# Power_board_rev_2.net
KiCad netlist of a schematic drawn in EAGLE
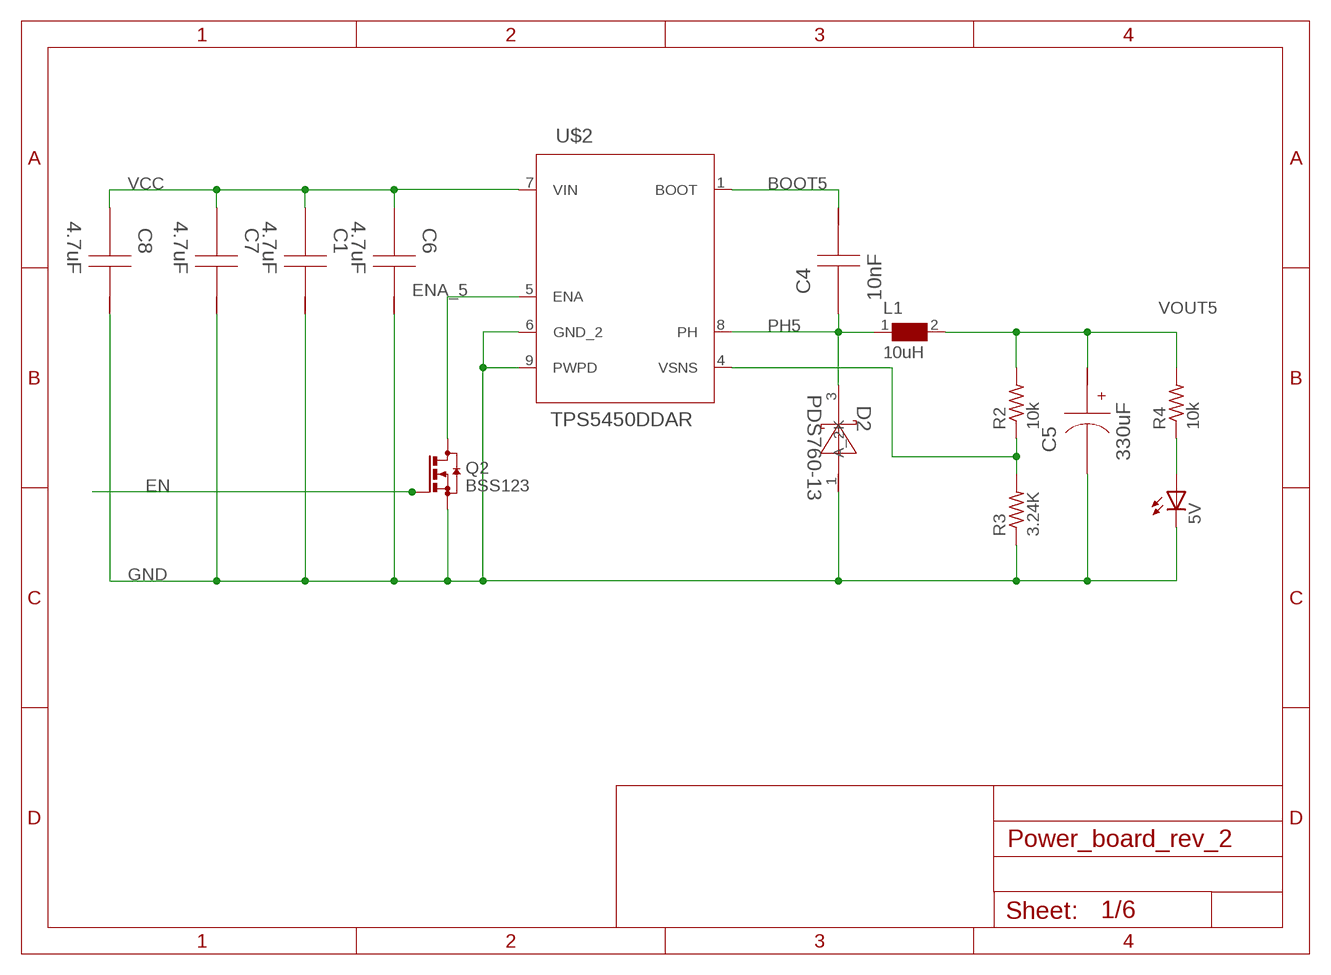
[diagram p0: schematic, sheet 1]
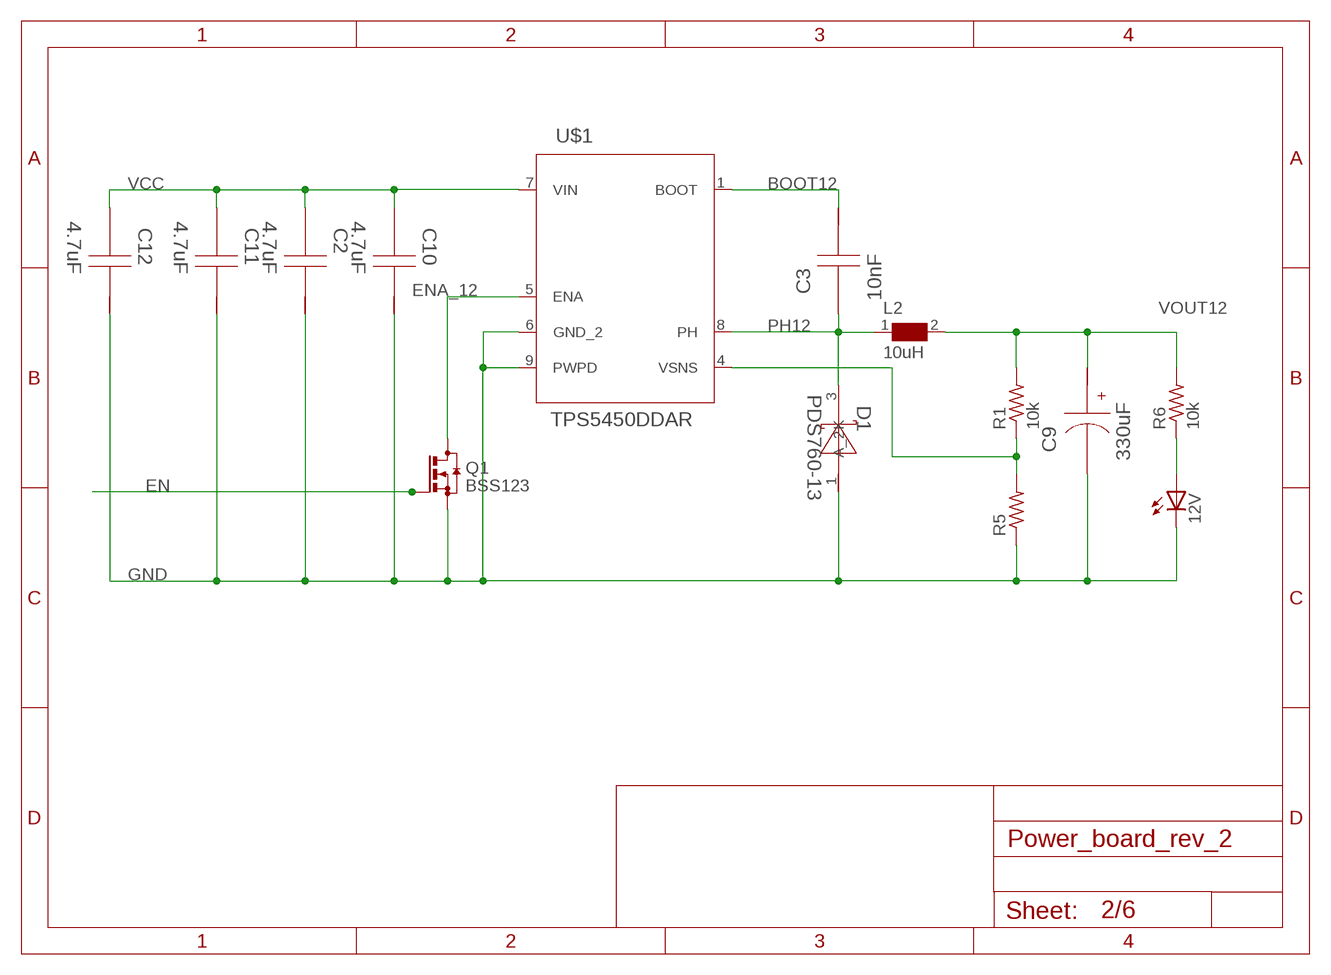
[diagram p1: schematic, sheet 2]
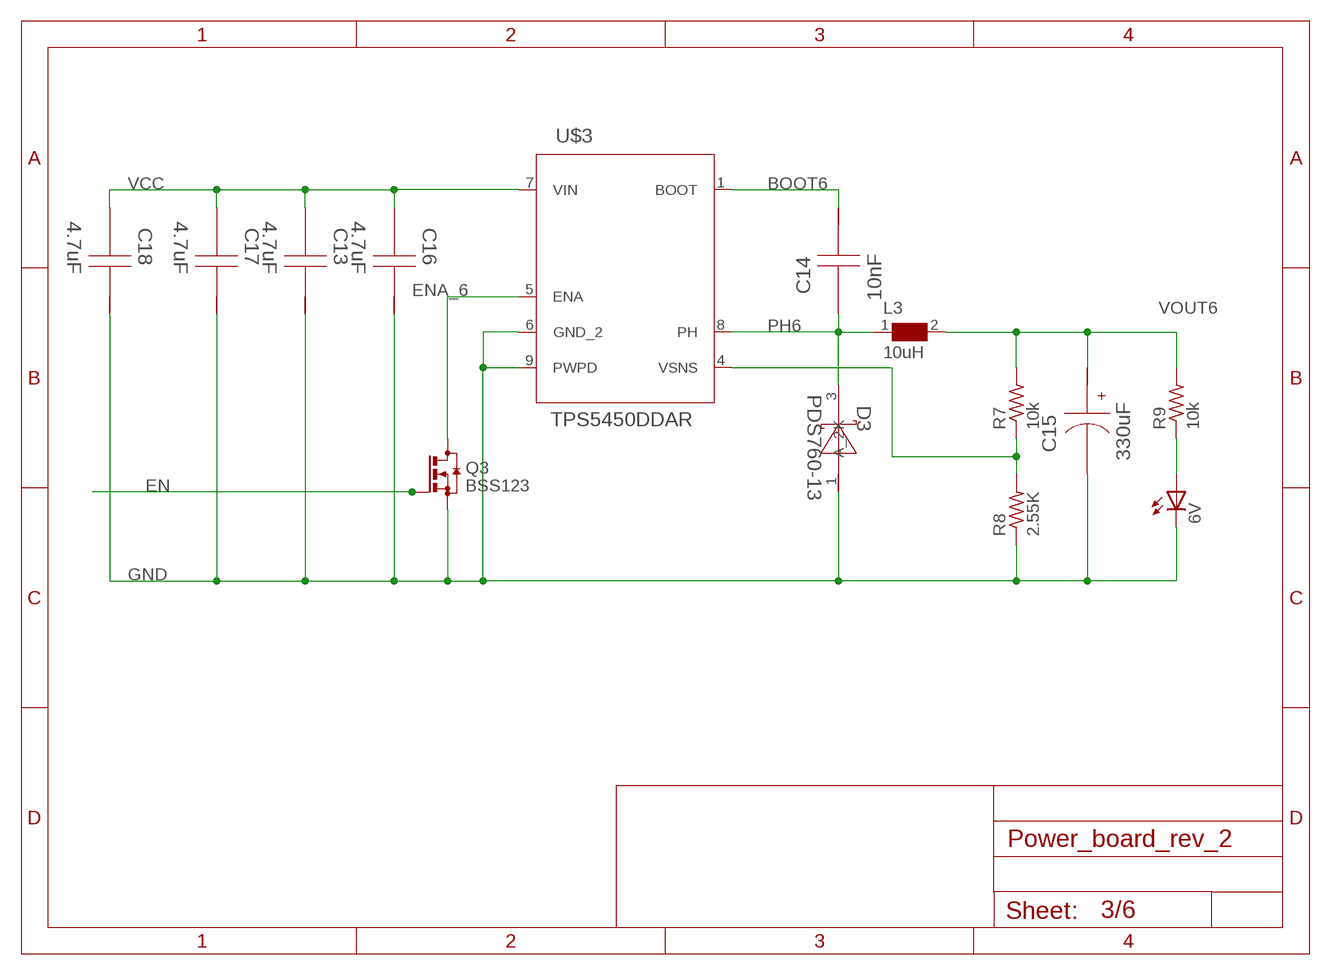
[diagram p2: schematic, sheet 3]
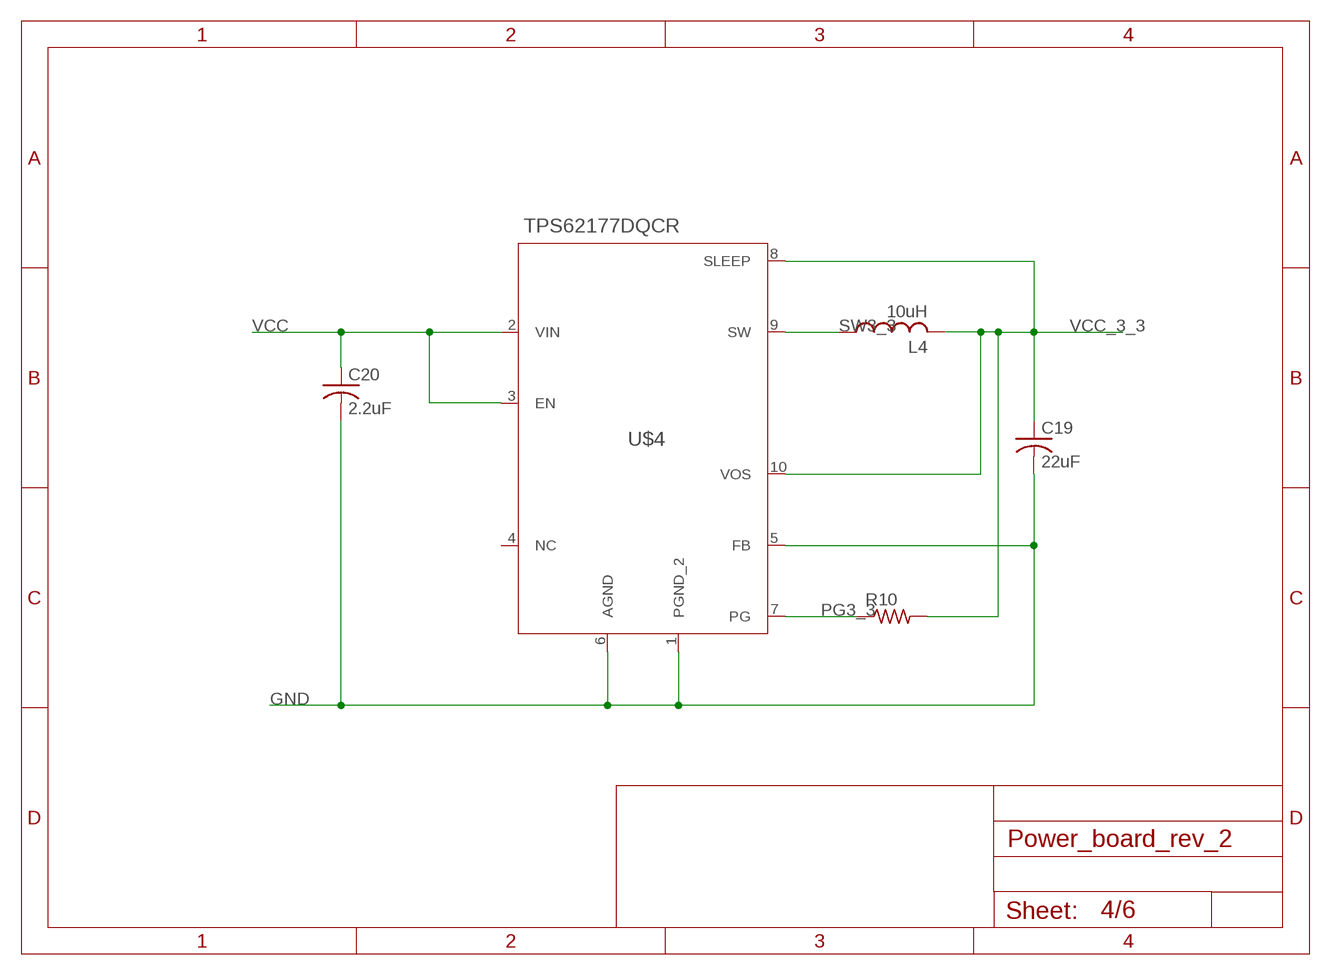
[diagram p3: schematic, sheet 4]
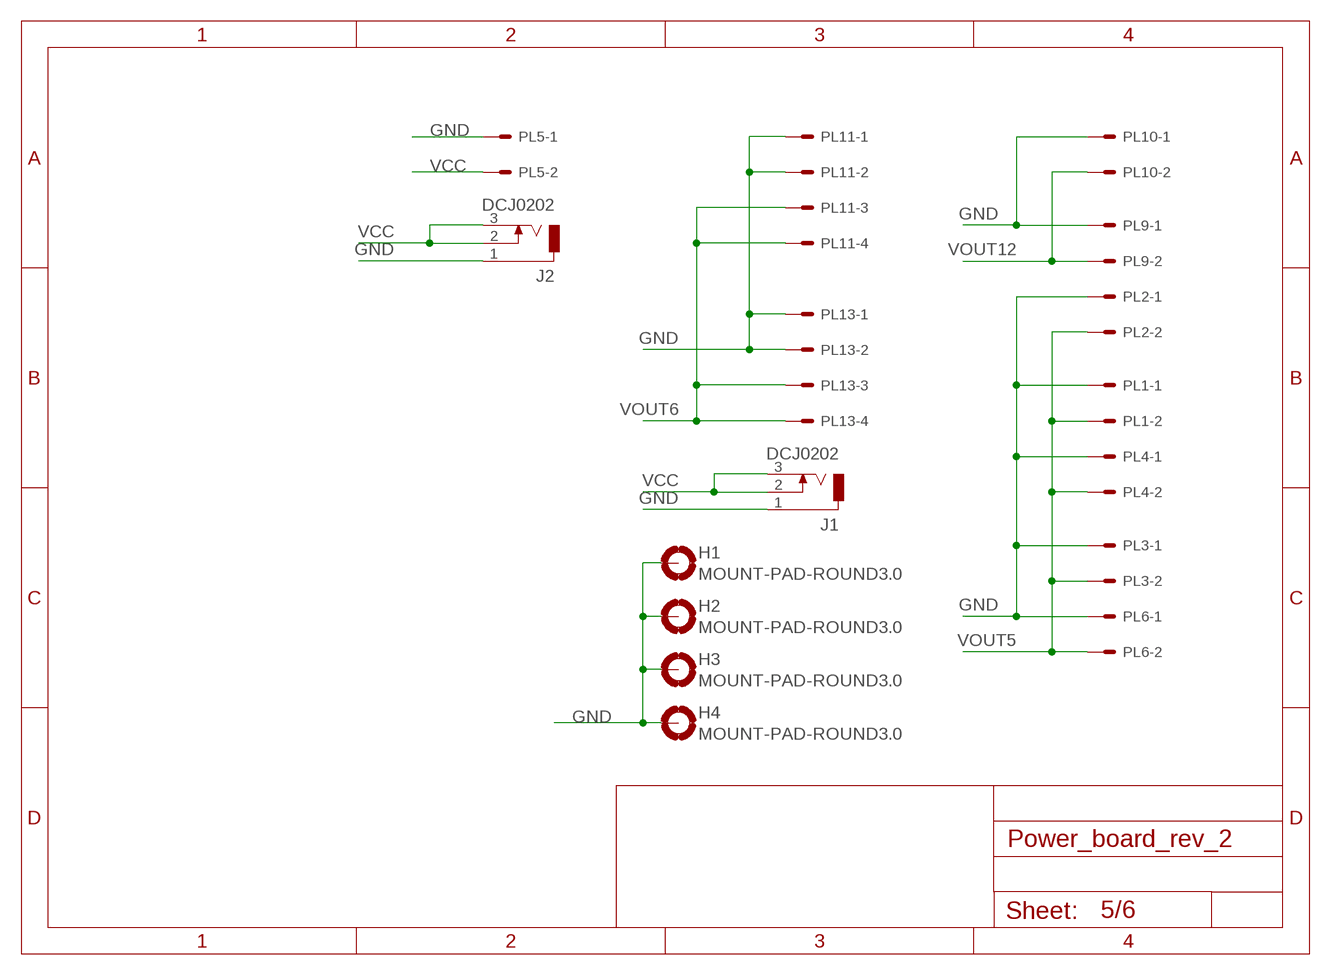
[diagram p4: schematic, sheet 5]
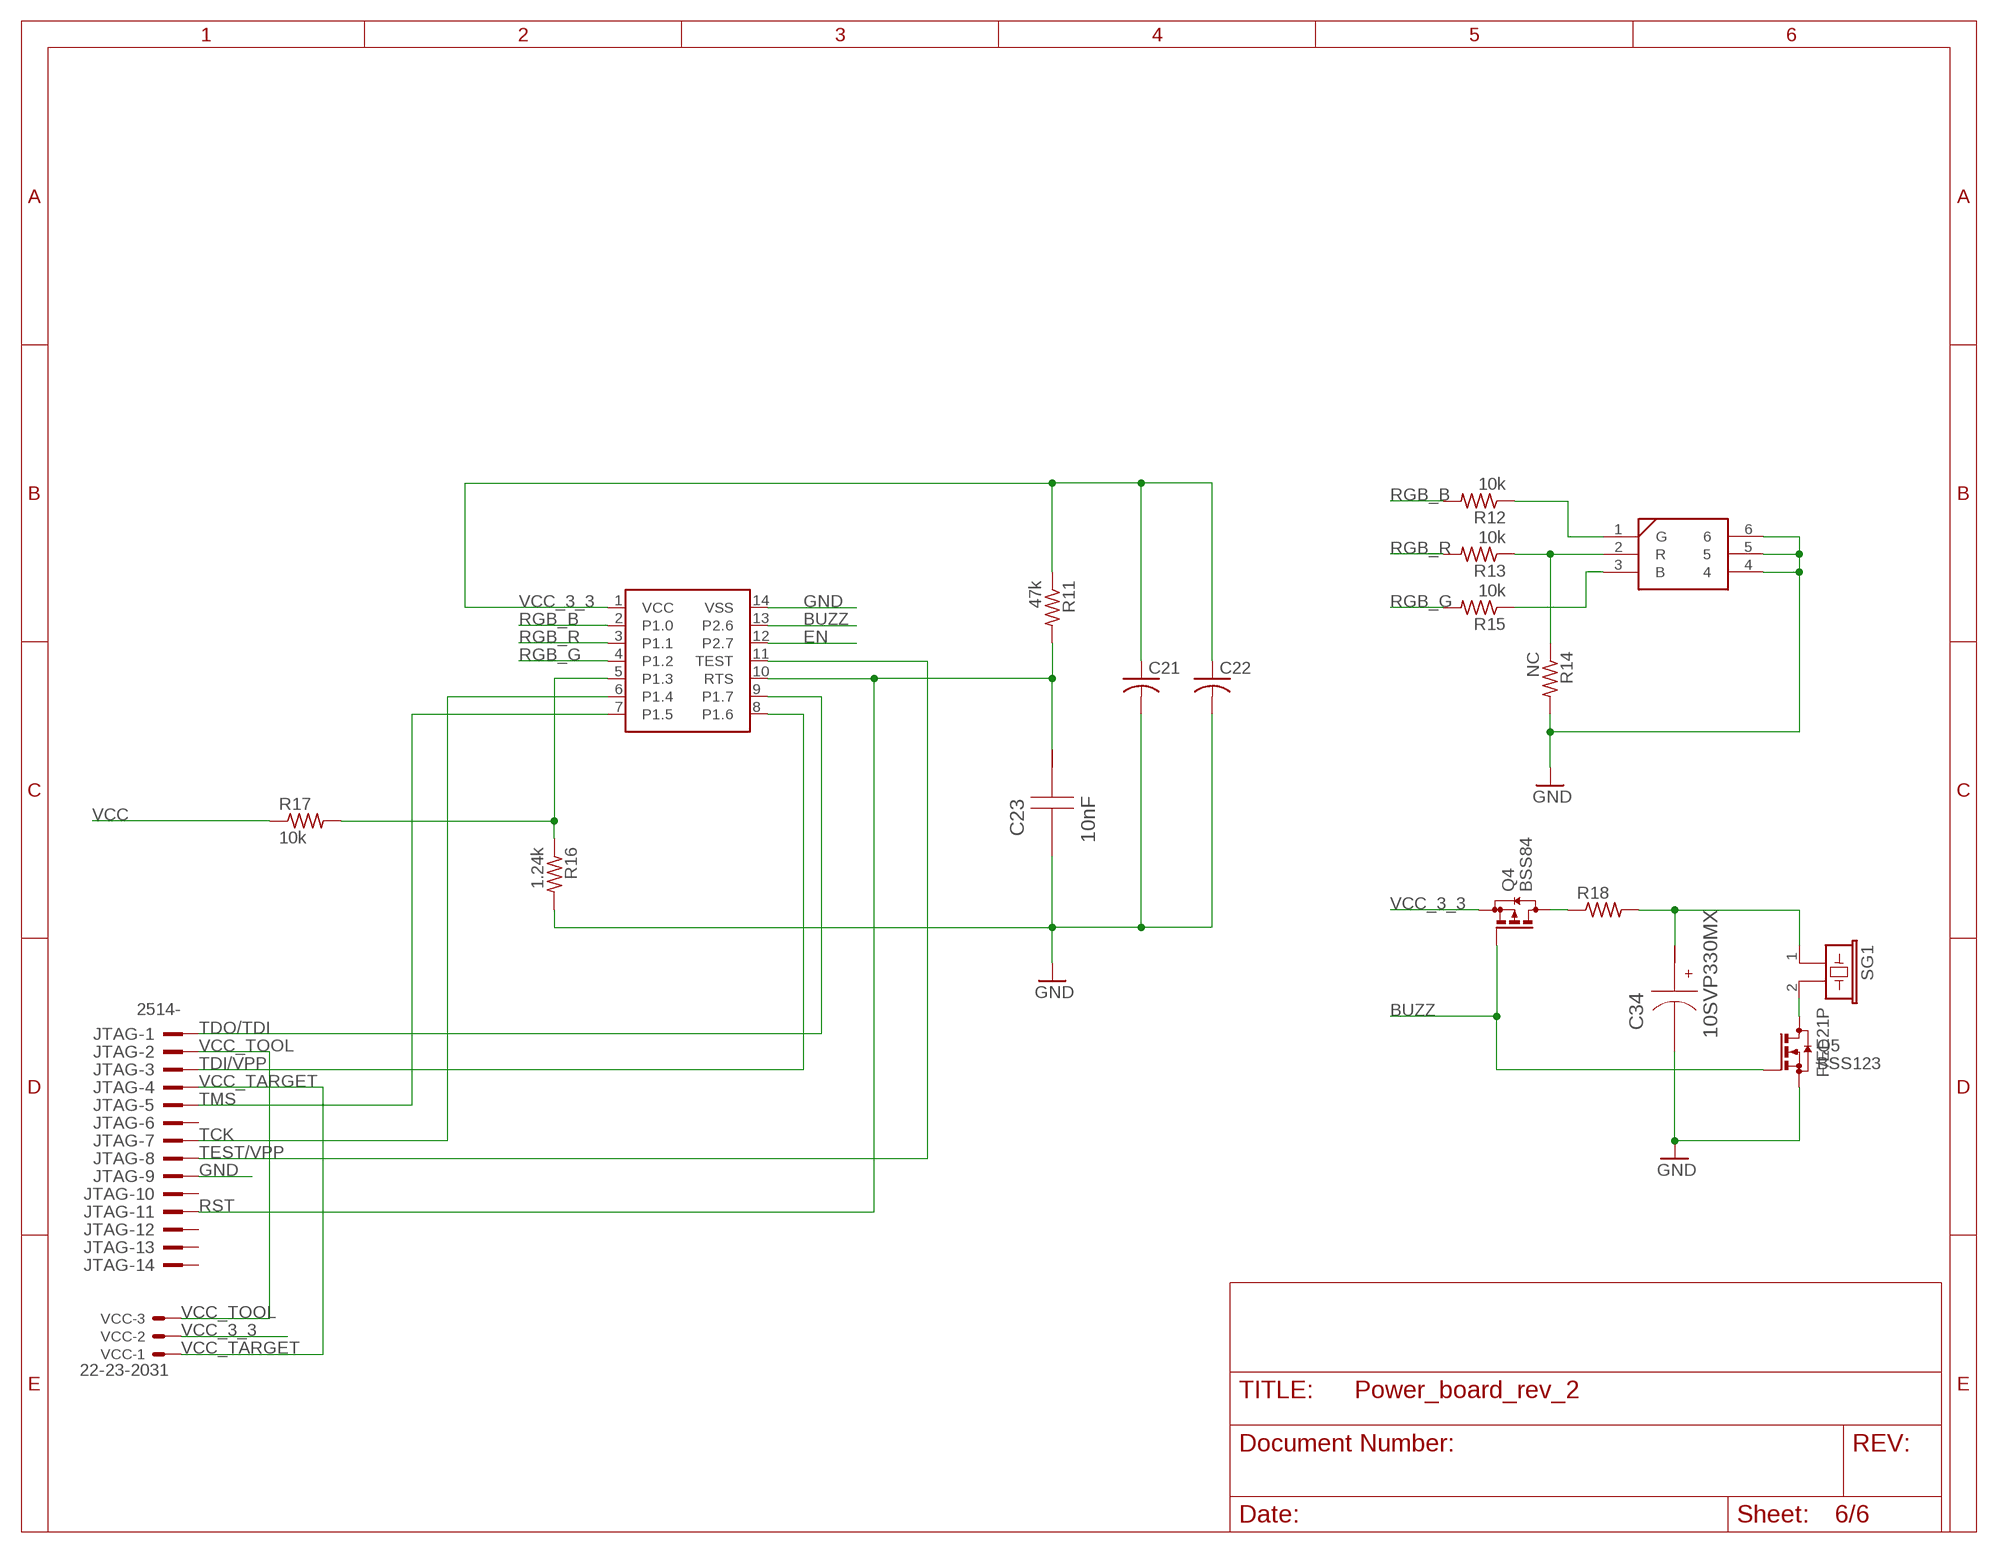
[diagram p5: schematic, sheet 6]

(export (version "E")
  (design (tool "Eeschema 10.0.6"))
  (components
    (comp (ref "6V")
      (value "LEDSML1206")
      (footprint "eagle-import:SML1206")
      (libsource (lib "eagle-import") (part "LEDSML1206"))
    )
    (comp (ref "C13")
      (value "4.7uF")
      (footprint "eagle-import:1206")
      (fields (field (name "MANUFACTURER_PART_NUMBER") "GRM31CR71H475KA12L"))
      (libsource (lib "eagle-import") (part "GRM31CR71H475KA12L"))
    )
    (comp (ref "C14")
      (value "10nF")
      (footprint "eagle-import:0805")
      (fields (field (name "MANUFACTURER_PART_NUMBER") "C0805C103K5RACTU"))
      (libsource (lib "eagle-import") (part "C0805C103K5RACTU"))
    )
    (comp (ref "C15")
      (value "330uF")
      (footprint "eagle-import:SM_RADIAL_10AMM")
      (fields (field (name "MANUFACTURER_PART_NUMBER") "10SVP330MX"))
      (libsource (lib "eagle-import") (part "10SVP330MX"))
    )
    (comp (ref "C16")
      (value "4.7uF")
      (footprint "eagle-import:1206")
      (fields (field (name "MANUFACTURER_PART_NUMBER") "GRM31CR71H475KA12L"))
      (libsource (lib "eagle-import") (part "GRM31CR71H475KA12L"))
    )
    (comp (ref "C17")
      (value "4.7uF")
      (footprint "eagle-import:1206")
      (fields (field (name "MANUFACTURER_PART_NUMBER") "GRM31CR71H475KA12L"))
      (libsource (lib "eagle-import") (part "GRM31CR71H475KA12L"))
    )
    (comp (ref "C18")
      (value "4.7uF")
      (footprint "eagle-import:1206")
      (fields (field (name "MANUFACTURER_PART_NUMBER") "GRM31CR71H475KA12L"))
      (libsource (lib "eagle-import") (part "GRM31CR71H475KA12L"))
    )
    (comp (ref "D3")
      (value "PDS760-13")
      (footprint "eagle-import:POWERDI5")
      (libsource (lib "eagle-import") (part "PDS760-13"))
    )
    (comp (ref "L3")
      (value "10uH")
      (footprint "eagle-import:WE-HCC_1090")
      (fields (field (name "MPN") "7443331000"))
      (libsource (lib "eagle-import") (part "WE-HCC_1090-7443331000"))
    )
    (comp (ref "Q3")
      (value "BSS123")
      (footprint "eagle-import:SOT23")
      (libsource (lib "eagle-import") (part "BSS123"))
    )
    (comp (ref "R7")
      (value "10k")
      (footprint "eagle-import:R1206")
      (libsource (lib "eagle-import") (part "R-US_R1206"))
    )
    (comp (ref "R8")
      (value "2.55K")
      (footprint "eagle-import:R1206")
      (libsource (lib "eagle-import") (part "R-US_R1206"))
    )
    (comp (ref "R9")
      (value "10k")
      (footprint "eagle-import:R1206")
      (libsource (lib "eagle-import") (part "R-US_R1206"))
    )
    (comp (ref "U$3")
      (value "TPS5450DDAR")
      (footprint "eagle-import:R-PDSO-G8")
      (fields (field (name "MANUFACTURER_PART_NUMBER") "TPS5450DDA"))
      (libsource (lib "eagle-import") (part "TPS5450DDAR"))
    )
    (comp (ref "C21")
      (value "C-USC1206K")
      (footprint "eagle-import:C1206K")
      (libsource (lib "eagle-import") (part "C-USC1206K"))
    )
    (comp (ref "C22")
      (value "C-USC1206K")
      (footprint "eagle-import:C1206K")
      (libsource (lib "eagle-import") (part "C-USC1206K"))
    )
    (comp (ref "C23")
      (value "10nF")
      (footprint "eagle-import:0805")
      (fields (field (name "MANUFACTURER_PART_NUMBER") "C0805C103K5RACTU"))
      (libsource (lib "eagle-import") (part "C0805C103K5RACTU"))
    )
    (comp (ref "C34")
      (value "10SVP330MX")
      (footprint "eagle-import:SM_RADIAL_10AMM")
      (libsource (lib "eagle-import") (part "10SVP330MX"))
    )
    (comp (ref "JTAG")
      (value "2514-")
      (footprint "eagle-import:PAK100_2500-14")
      (libsource (lib "eagle-import") (part "2514-"))
    )
    (comp (ref "Q4")
      (value "BSS84")
      (footprint "eagle-import:SOT23")
      (libsource (lib "eagle-import") (part "BSS84"))
    )
    (comp (ref "Q5")
      (value "BSS123")
      (footprint "eagle-import:SOT23")
      (libsource (lib "eagle-import") (part "BSS123"))
    )
    (comp (ref "R11")
      (value "47k")
      (footprint "eagle-import:R1206W")
      (libsource (lib "eagle-import") (part "R-US_R1206W"))
    )
    (comp (ref "R12")
      (value "10k")
      (footprint "eagle-import:R1206W")
      (libsource (lib "eagle-import") (part "R-US_R1206W"))
    )
    (comp (ref "R13")
      (value "10k")
      (footprint "eagle-import:R1206W")
      (libsource (lib "eagle-import") (part "R-US_R1206W"))
    )
    (comp (ref "R14")
      (value "NC")
      (footprint "eagle-import:R1206W")
      (libsource (lib "eagle-import") (part "R-US_R1206W"))
    )
    (comp (ref "R15")
      (value "10k")
      (footprint "eagle-import:R1206W")
      (libsource (lib "eagle-import") (part "R-US_R1206W"))
    )
    (comp (ref "R16")
      (value "1.24k")
      (footprint "eagle-import:R1206W")
      (libsource (lib "eagle-import") (part "R-US_R1206W"))
    )
    (comp (ref "R17")
      (value "10k")
      (footprint "eagle-import:R1206W")
      (libsource (lib "eagle-import") (part "R-US_R1206W"))
    )
    (comp (ref "R18")
      (value "R-US_R1206W")
      (footprint "eagle-import:R1206W")
      (libsource (lib "eagle-import") (part "R-US_R1206W"))
    )
    (comp (ref "SG1")
      (value "F/EE21P")
      (footprint "eagle-import:F_EE21P")
      (libsource (lib "eagle-import") (part "F/EE21P"))
    )
    (comp (ref "U$5")
      (value "MSP430F20X3")
      (footprint "eagle-import:TSSOP-14")
      (libsource (lib "eagle-import") (part "MSP430F20X3"))
    )
    (comp (ref "U$7")
      (value "RGB")
      (footprint "eagle-import:RGB_SMD")
      (libsource (lib "eagle-import") (part "RGB"))
    )
    (comp (ref "VCC")
      (value "22-23-2031")
      (footprint "eagle-import:22-23-2031")
      (fields (field (name "MF") "MOLEX"))
      (libsource (lib "eagle-import") (part "22-23-2031"))
    )
    (comp (ref "5V")
      (value "LEDSML1206")
      (footprint "eagle-import:SML1206")
      (libsource (lib "eagle-import") (part "LEDSML1206"))
    )
    (comp (ref "C1")
      (value "4.7uF")
      (footprint "eagle-import:1206")
      (fields (field (name "MANUFACTURER_PART_NUMBER") "GRM31CR71H475KA12L"))
      (libsource (lib "eagle-import") (part "GRM31CR71H475KA12L"))
    )
    (comp (ref "C4")
      (value "10nF")
      (footprint "eagle-import:0805")
      (fields (field (name "MANUFACTURER_PART_NUMBER") "C0805C103K5RACTU"))
      (libsource (lib "eagle-import") (part "C0805C103K5RACTU"))
    )
    (comp (ref "C5")
      (value "330uF")
      (footprint "eagle-import:SM_RADIAL_10AMM")
      (fields (field (name "MANUFACTURER_PART_NUMBER") "10SVP330MX"))
      (libsource (lib "eagle-import") (part "10SVP330MX"))
    )
    (comp (ref "C6")
      (value "4.7uF")
      (footprint "eagle-import:1206")
      (fields (field (name "MANUFACTURER_PART_NUMBER") "GRM31CR71H475KA12L"))
      (libsource (lib "eagle-import") (part "GRM31CR71H475KA12L"))
    )
    (comp (ref "C7")
      (value "4.7uF")
      (footprint "eagle-import:1206")
      (fields (field (name "MANUFACTURER_PART_NUMBER") "GRM31CR71H475KA12L"))
      (libsource (lib "eagle-import") (part "GRM31CR71H475KA12L"))
    )
    (comp (ref "C8")
      (value "4.7uF")
      (footprint "eagle-import:1206")
      (fields (field (name "MANUFACTURER_PART_NUMBER") "GRM31CR71H475KA12L"))
      (libsource (lib "eagle-import") (part "GRM31CR71H475KA12L"))
    )
    (comp (ref "D2")
      (value "PDS760-13")
      (footprint "eagle-import:POWERDI5")
      (libsource (lib "eagle-import") (part "PDS760-13"))
    )
    (comp (ref "L1")
      (value "10uH")
      (footprint "eagle-import:WE-HCC_1090")
      (fields (field (name "MPN") "7443331000"))
      (libsource (lib "eagle-import") (part "WE-HCC_1090-7443331000"))
    )
    (comp (ref "Q2")
      (value "BSS123")
      (footprint "eagle-import:SOT23")
      (libsource (lib "eagle-import") (part "BSS123"))
    )
    (comp (ref "R2")
      (value "10k")
      (footprint "eagle-import:R1206")
      (libsource (lib "eagle-import") (part "R-US_R1206"))
    )
    (comp (ref "R3")
      (value "3.24K")
      (footprint "eagle-import:R1206")
      (libsource (lib "eagle-import") (part "R-US_R1206"))
    )
    (comp (ref "R4")
      (value "10k")
      (footprint "eagle-import:R1206")
      (libsource (lib "eagle-import") (part "R-US_R1206"))
    )
    (comp (ref "U$2")
      (value "TPS5450DDAR")
      (footprint "eagle-import:R-PDSO-G8")
      (fields (field (name "MANUFACTURER_PART_NUMBER") "TPS5450DDA"))
      (libsource (lib "eagle-import") (part "TPS5450DDAR"))
    )
    (comp (ref "C19")
      (value "22uF")
      (footprint "eagle-import:C0805")
      (libsource (lib "eagle-import") (part "C-USC0805"))
    )
    (comp (ref "C20")
      (value "2.2uF")
      (footprint "eagle-import:C1210K")
      (libsource (lib "eagle-import") (part "C-USC1210K"))
    )
    (comp (ref "L4")
      (value "10uH")
      (footprint "eagle-import:POWER-CHOKE_WE-TPC")
      (libsource (lib "eagle-import") (part "L-USWE-TPC"))
    )
    (comp (ref "R10")
      (value "R-US_R0402")
      (footprint "eagle-import:R0402")
      (libsource (lib "eagle-import") (part "R-US_R0402"))
    )
    (comp (ref "U$4")
      (value "TPS62177DQCR")
      (footprint "eagle-import:R-PWSON-N10")
      (fields (field (name "MANUFACTURER_PART_NUMBER") "TPS62175DQCR"))
      (libsource (lib "eagle-import") (part "TPS62177DQCR"))
    )
    (comp (ref "H1")
      (value "MOUNT-PAD-ROUND3.0")
      (footprint "eagle-import:3,0-PAD")
      (libsource (lib "eagle-import") (part "MOUNT-PAD-ROUND3.0"))
    )
    (comp (ref "H2")
      (value "MOUNT-PAD-ROUND3.0")
      (footprint "eagle-import:3,0-PAD")
      (libsource (lib "eagle-import") (part "MOUNT-PAD-ROUND3.0"))
    )
    (comp (ref "H3")
      (value "MOUNT-PAD-ROUND3.0")
      (footprint "eagle-import:3,0-PAD")
      (libsource (lib "eagle-import") (part "MOUNT-PAD-ROUND3.0"))
    )
    (comp (ref "H4")
      (value "MOUNT-PAD-ROUND3.0")
      (footprint "eagle-import:3,0-PAD")
      (libsource (lib "eagle-import") (part "MOUNT-PAD-ROUND3.0"))
    )
    (comp (ref "J1")
      (value "DCJ0202")
      (footprint "eagle-import:DCJ0202")
      (libsource (lib "eagle-import") (part "DCJ0202"))
    )
    (comp (ref "J2")
      (value "DCJ0202")
      (footprint "eagle-import:DCJ0202")
      (libsource (lib "eagle-import") (part "DCJ0202"))
    )
    (comp (ref "PL1")
      (value "555X-2H")
      (footprint "eagle-import:5569-2")
      (libsource (lib "eagle-import") (part "555X-2H"))
    )
    (comp (ref "PL2")
      (value "555X-2H")
      (footprint "eagle-import:5569-2")
      (libsource (lib "eagle-import") (part "555X-2H"))
    )
    (comp (ref "PL3")
      (value "555X-2H")
      (footprint "eagle-import:5569-2")
      (libsource (lib "eagle-import") (part "555X-2H"))
    )
    (comp (ref "PL4")
      (value "555X-2H")
      (footprint "eagle-import:5569-2")
      (libsource (lib "eagle-import") (part "555X-2H"))
    )
    (comp (ref "PL5")
      (value "555X-2H")
      (footprint "eagle-import:5569-2")
      (libsource (lib "eagle-import") (part "555X-2H"))
    )
    (comp (ref "PL6")
      (value "555X-2H")
      (footprint "eagle-import:5569-2")
      (libsource (lib "eagle-import") (part "555X-2H"))
    )
    (comp (ref "PL9")
      (value "555X-2H")
      (footprint "eagle-import:5569-2")
      (libsource (lib "eagle-import") (part "555X-2H"))
    )
    (comp (ref "PL10")
      (value "555X-2H")
      (footprint "eagle-import:5569-2")
      (libsource (lib "eagle-import") (part "555X-2H"))
    )
    (comp (ref "PL11")
      (value "555X-4H")
      (footprint "eagle-import:5569-4")
      (libsource (lib "eagle-import") (part "555X-4H"))
    )
    (comp (ref "PL13")
      (value "555X-4H")
      (footprint "eagle-import:5569-4")
      (libsource (lib "eagle-import") (part "555X-4H"))
    )
    (comp (ref "12V")
      (value "LEDSML1206")
      (footprint "eagle-import:SML1206")
      (libsource (lib "eagle-import") (part "LEDSML1206"))
    )
    (comp (ref "C2")
      (value "4.7uF")
      (footprint "eagle-import:1206")
      (fields (field (name "MANUFACTURER_PART_NUMBER") "GRM31CR71H475KA12L"))
      (libsource (lib "eagle-import") (part "GRM31CR71H475KA12L"))
    )
    (comp (ref "C3")
      (value "10nF")
      (footprint "eagle-import:0805")
      (fields (field (name "MANUFACTURER_PART_NUMBER") "C0805C103K5RACTU"))
      (libsource (lib "eagle-import") (part "C0805C103K5RACTU"))
    )
    (comp (ref "C9")
      (value "330uF")
      (footprint "eagle-import:SM_RADIAL_10AMM")
      (fields (field (name "MANUFACTURER_PART_NUMBER") "10SVP330MX"))
      (libsource (lib "eagle-import") (part "10SVP330MX"))
    )
    (comp (ref "C10")
      (value "4.7uF")
      (footprint "eagle-import:1206")
      (fields (field (name "MANUFACTURER_PART_NUMBER") "GRM31CR71H475KA12L"))
      (libsource (lib "eagle-import") (part "GRM31CR71H475KA12L"))
    )
    (comp (ref "C11")
      (value "4.7uF")
      (footprint "eagle-import:1206")
      (fields (field (name "MANUFACTURER_PART_NUMBER") "GRM31CR71H475KA12L"))
      (libsource (lib "eagle-import") (part "GRM31CR71H475KA12L"))
    )
    (comp (ref "C12")
      (value "4.7uF")
      (footprint "eagle-import:1206")
      (fields (field (name "MANUFACTURER_PART_NUMBER") "GRM31CR71H475KA12L"))
      (libsource (lib "eagle-import") (part "GRM31CR71H475KA12L"))
    )
    (comp (ref "D1")
      (value "PDS760-13")
      (footprint "eagle-import:POWERDI5")
      (libsource (lib "eagle-import") (part "PDS760-13"))
    )
    (comp (ref "L2")
      (value "10uH")
      (footprint "eagle-import:WE-HCC_1090")
      (fields (field (name "MPN") "7443331000"))
      (libsource (lib "eagle-import") (part "WE-HCC_1090-7443331000"))
    )
    (comp (ref "Q1")
      (value "BSS123")
      (footprint "eagle-import:SOT23")
      (libsource (lib "eagle-import") (part "BSS123"))
    )
    (comp (ref "R1")
      (value "10k")
      (footprint "eagle-import:R1206")
      (libsource (lib "eagle-import") (part "R-US_R1206"))
    )
    (comp (ref "R5")
      (value "R-US_R1206")
      (footprint "eagle-import:R1206")
      (libsource (lib "eagle-import") (part "R-US_R1206"))
    )
    (comp (ref "R6")
      (value "10k")
      (footprint "eagle-import:R1206")
      (libsource (lib "eagle-import") (part "R-US_R1206"))
    )
    (comp (ref "U$1")
      (value "TPS5450DDAR")
      (footprint "eagle-import:R-PDSO-G8")
      (fields (field (name "MANUFACTURER_PART_NUMBER") "TPS5450DDA"))
      (libsource (lib "eagle-import") (part "TPS5450DDAR"))
    )
  )
  (nets
    (net (code "1") (name "BOOT5") (class "Default")
      (node (ref "C4") (pin "1") (pinfunction "1_1") (pintype "passive"))
      (node (ref "U$2") (pin "1") (pinfunction "BOOT_1") (pintype "passive"))
    )
    (net (code "2") (name "BOOT6") (class "Default")
      (node (ref "C14") (pin "1") (pinfunction "1_1") (pintype "passive"))
      (node (ref "U$3") (pin "1") (pinfunction "BOOT_1") (pintype "passive"))
    )
    (net (code "3") (name "BOOT12") (class "Default")
      (node (ref "C3") (pin "1") (pinfunction "1_1") (pintype "passive"))
      (node (ref "U$1") (pin "1") (pinfunction "BOOT_1") (pintype "passive"))
    )
    (net (code "4") (name "BUZZ") (class "Default")
      (node (ref "Q4") (pin "1") (pinfunction "G_1") (pintype "passive"))
      (node (ref "Q5") (pin "1") (pinfunction "G_1") (pintype "passive"))
      (node (ref "U$5") (pin "13") (pinfunction "P2.6_13") (pintype "bidirectional"))
    )
    (net (code "5") (name "EN") (class "Default")
      (node (ref "Q1") (pin "1") (pinfunction "G_1") (pintype "passive"))
      (node (ref "Q2") (pin "1") (pinfunction "G_1") (pintype "passive"))
      (node (ref "Q3") (pin "1") (pinfunction "G_1") (pintype "passive"))
      (node (ref "U$5") (pin "12") (pinfunction "P2.7_12") (pintype "bidirectional"))
    )
    (net (code "6") (name "ENA_5") (class "Default")
      (node (ref "Q2") (pin "3") (pinfunction "D_3") (pintype "passive"))
      (node (ref "U$2") (pin "5") (pinfunction "ENA_5") (pintype "passive"))
    )
    (net (code "7") (name "ENA_6") (class "Default")
      (node (ref "Q3") (pin "3") (pinfunction "D_3") (pintype "passive"))
      (node (ref "U$3") (pin "5") (pinfunction "ENA_5") (pintype "passive"))
    )
    (net (code "8") (name "ENA_12") (class "Default")
      (node (ref "Q1") (pin "3") (pinfunction "D_3") (pintype "passive"))
      (node (ref "U$1") (pin "5") (pinfunction "ENA_5") (pintype "passive"))
    )
    (net (code "9") (name "GND") (class "Default")
      (node (ref "12V") (pin "C") (pinfunction "C_C") (pintype "passive"))
      (node (ref "5V") (pin "C") (pinfunction "C_C") (pintype "passive"))
      (node (ref "6V") (pin "C") (pinfunction "C_C") (pintype "passive"))
      (node (ref "C1") (pin "1") (pinfunction "1_1") (pintype "passive"))
      (node (ref "C10") (pin "1") (pinfunction "1_1") (pintype "passive"))
      (node (ref "C11") (pin "1") (pinfunction "1_1") (pintype "passive"))
      (node (ref "C12") (pin "1") (pinfunction "1_1") (pintype "passive"))
      (node (ref "C13") (pin "1") (pinfunction "1_1") (pintype "passive"))
      (node (ref "C15") (pin "2") (pinfunction "-_2") (pintype "passive"))
      (node (ref "C16") (pin "1") (pinfunction "1_1") (pintype "passive"))
      (node (ref "C17") (pin "1") (pinfunction "1_1") (pintype "passive"))
      (node (ref "C18") (pin "1") (pinfunction "1_1") (pintype "passive"))
      (node (ref "C19") (pin "2") (pinfunction "2_2") (pintype "passive"))
      (node (ref "C2") (pin "1") (pinfunction "1_1") (pintype "passive"))
      (node (ref "C20") (pin "2") (pinfunction "2_2") (pintype "passive"))
      (node (ref "C21") (pin "2") (pinfunction "2_2") (pintype "passive"))
      (node (ref "C22") (pin "2") (pinfunction "2_2") (pintype "passive"))
      (node (ref "C23") (pin "2") (pinfunction "2_2") (pintype "passive"))
      (node (ref "C34") (pin "2") (pinfunction "-_2") (pintype "passive"))
      (node (ref "C5") (pin "2") (pinfunction "-_2") (pintype "passive"))
      (node (ref "C6") (pin "1") (pinfunction "1_1") (pintype "passive"))
      (node (ref "C7") (pin "1") (pinfunction "1_1") (pintype "passive"))
      (node (ref "C8") (pin "1") (pinfunction "1_1") (pintype "passive"))
      (node (ref "C9") (pin "2") (pinfunction "-_2") (pintype "passive"))
      (node (ref "D1") (pin "1") (pinfunction "A_2_1") (pintype "passive"))
      (node (ref "D2") (pin "1") (pinfunction "A_2_1") (pintype "passive"))
      (node (ref "D3") (pin "1") (pinfunction "A_2_1") (pintype "passive"))
      (node (ref "H1") (pin "B3,0") (pinfunction "MOUNT_B3,0") (pintype "passive"))
      (node (ref "H2") (pin "B3,0") (pinfunction "MOUNT_B3,0") (pintype "passive"))
      (node (ref "H3") (pin "B3,0") (pinfunction "MOUNT_B3,0") (pintype "passive"))
      (node (ref "H4") (pin "B3,0") (pinfunction "MOUNT_B3,0") (pintype "passive"))
      (node (ref "J1") (pin "1") (pinfunction "1_1") (pintype "passive"))
      (node (ref "J2") (pin "1") (pinfunction "1_1") (pintype "passive"))
      (node (ref "JTAG") (pin "9") (pinfunction "KL_9") (pintype "passive"))
      (node (ref "PL1") (pin "1") (pinfunction "S_1") (pintype "passive"))
      (node (ref "PL10") (pin "1") (pinfunction "S_1") (pintype "passive"))
      (node (ref "PL11") (pin "1") (pinfunction "S_1") (pintype "passive"))
      (node (ref "PL11") (pin "2") (pinfunction "S_2") (pintype "passive"))
      (node (ref "PL13") (pin "1") (pinfunction "S_1") (pintype "passive"))
      (node (ref "PL13") (pin "2") (pinfunction "S_2") (pintype "passive"))
      (node (ref "PL2") (pin "1") (pinfunction "S_1") (pintype "passive"))
      (node (ref "PL3") (pin "1") (pinfunction "S_1") (pintype "passive"))
      (node (ref "PL4") (pin "1") (pinfunction "S_1") (pintype "passive"))
      (node (ref "PL5") (pin "1") (pinfunction "S_1") (pintype "passive"))
      (node (ref "PL6") (pin "1") (pinfunction "S_1") (pintype "passive"))
      (node (ref "PL9") (pin "1") (pinfunction "S_1") (pintype "passive"))
      (node (ref "Q1") (pin "2") (pinfunction "S_2") (pintype "passive"))
      (node (ref "Q2") (pin "2") (pinfunction "S_2") (pintype "passive"))
      (node (ref "Q3") (pin "2") (pinfunction "S_2") (pintype "passive"))
      (node (ref "Q5") (pin "2") (pinfunction "S_2") (pintype "passive"))
      (node (ref "R14") (pin "2") (pinfunction "2_2") (pintype "passive"))
      (node (ref "R16") (pin "2") (pinfunction "2_2") (pintype "passive"))
      (node (ref "R3") (pin "1") (pinfunction "1_1") (pintype "passive"))
      (node (ref "R5") (pin "1") (pinfunction "1_1") (pintype "passive"))
      (node (ref "R8") (pin "1") (pinfunction "1_1") (pintype "passive"))
      (node (ref "U$1") (pin "6") (pinfunction "GND_2_6") (pintype "passive"))
      (node (ref "U$1") (pin "9") (pinfunction "PWPD_9") (pintype "passive"))
      (node (ref "U$2") (pin "6") (pinfunction "GND_2_6") (pintype "passive"))
      (node (ref "U$2") (pin "9") (pinfunction "PWPD_9") (pintype "passive"))
      (node (ref "U$3") (pin "6") (pinfunction "GND_2_6") (pintype "passive"))
      (node (ref "U$3") (pin "9") (pinfunction "PWPD_9") (pintype "passive"))
      (node (ref "U$4") (pin "1") (pinfunction "PGND_2_1") (pintype "passive"))
      (node (ref "U$4") (pin "5") (pinfunction "FB_5") (pintype "passive"))
      (node (ref "U$4") (pin "6") (pinfunction "AGND_6") (pintype "passive"))
      (node (ref "U$5") (pin "14") (pinfunction "VSS_14") (pintype "bidirectional"))
      (node (ref "U$7") (pin "4") (pinfunction "4_4") (pintype "bidirectional"))
      (node (ref "U$7") (pin "5") (pinfunction "5_5") (pintype "bidirectional"))
      (node (ref "U$7") (pin "6") (pinfunction "6_6") (pintype "bidirectional"))
    )
    (net (code "10") (name "Net-(5V-PadA)") (class "Default")
      (node (ref "5V") (pin "A") (pinfunction "A_A") (pintype "passive"))
      (node (ref "R4") (pin "1") (pinfunction "1_1") (pintype "passive"))
    )
    (net (code "11") (name "Net-(6V-PadA)") (class "Default")
      (node (ref "6V") (pin "A") (pinfunction "A_A") (pintype "passive"))
      (node (ref "R9") (pin "1") (pinfunction "1_1") (pintype "passive"))
    )
    (net (code "12") (name "Net-(12V-PadA)") (class "Default")
      (node (ref "12V") (pin "A") (pinfunction "A_A") (pintype "passive"))
      (node (ref "R6") (pin "1") (pinfunction "1_1") (pintype "passive"))
    )
    (net (code "13") (name "Net-(C34-+)") (class "Default")
      (node (ref "C34") (pin "1") (pinfunction "+_1") (pintype "passive"))
      (node (ref "R18") (pin "2") (pinfunction "2_2") (pintype "passive"))
      (node (ref "SG1") (pin "1") (pinfunction "1_1") (pintype "passive"))
    )
    (net (code "14") (name "Net-(Q4-D)") (class "Default")
      (node (ref "Q4") (pin "3") (pinfunction "D_3") (pintype "passive"))
      (node (ref "R18") (pin "1") (pinfunction "1_1") (pintype "passive"))
    )
    (net (code "15") (name "Net-(Q5-D)") (class "Default")
      (node (ref "Q5") (pin "3") (pinfunction "D_3") (pintype "passive"))
      (node (ref "SG1") (pin "2") (pinfunction "2_2") (pintype "passive"))
    )
    (net (code "16") (name "Net-(U$1-VSNS)") (class "Default")
      (node (ref "R1") (pin "1") (pinfunction "1_1") (pintype "passive"))
      (node (ref "R5") (pin "2") (pinfunction "2_2") (pintype "passive"))
      (node (ref "U$1") (pin "4") (pinfunction "VSNS_4") (pintype "passive"))
    )
    (net (code "17") (name "Net-(U$2-VSNS)") (class "Default")
      (node (ref "R2") (pin "1") (pinfunction "1_1") (pintype "passive"))
      (node (ref "R3") (pin "2") (pinfunction "2_2") (pintype "passive"))
      (node (ref "U$2") (pin "4") (pinfunction "VSNS_4") (pintype "passive"))
    )
    (net (code "18") (name "Net-(U$3-VSNS)") (class "Default")
      (node (ref "R7") (pin "1") (pinfunction "1_1") (pintype "passive"))
      (node (ref "R8") (pin "2") (pinfunction "2_2") (pintype "passive"))
      (node (ref "U$3") (pin "4") (pinfunction "VSNS_4") (pintype "passive"))
    )
    (net (code "19") (name "Net-(U$5-P1.3)") (class "Default")
      (node (ref "R16") (pin "1") (pinfunction "1_1") (pintype "passive"))
      (node (ref "R17") (pin "2") (pinfunction "2_2") (pintype "passive"))
      (node (ref "U$5") (pin "5") (pinfunction "P1.3_5") (pintype "bidirectional"))
    )
    (net (code "20") (name "Net-(U$7-B)") (class "Default")
      (node (ref "R15") (pin "1") (pinfunction "1_1") (pintype "passive"))
      (node (ref "U$7") (pin "3") (pinfunction "B_3") (pintype "bidirectional"))
    )
    (net (code "21") (name "Net-(U$7-G)") (class "Default")
      (node (ref "R12") (pin "1") (pinfunction "1_1") (pintype "passive"))
      (node (ref "U$7") (pin "1") (pinfunction "G_1") (pintype "bidirectional"))
    )
    (net (code "22") (name "Net-(U$7-R)") (class "Default")
      (node (ref "R13") (pin "1") (pinfunction "1_1") (pintype "passive"))
      (node (ref "R14") (pin "1") (pinfunction "1_1") (pintype "passive"))
      (node (ref "U$7") (pin "2") (pinfunction "R_2") (pintype "bidirectional"))
    )
    (net (code "23") (name "PG3_3") (class "Default")
      (node (ref "R10") (pin "1") (pinfunction "1_1") (pintype "passive"))
      (node (ref "U$4") (pin "7") (pinfunction "PG_7") (pintype "passive"))
    )
    (net (code "24") (name "PH5") (class "Default")
      (node (ref "C4") (pin "2") (pinfunction "2_2") (pintype "passive"))
      (node (ref "D2") (pin "3") (pinfunction "K_3") (pintype "passive"))
      (node (ref "L1") (pin "1") (pinfunction "1_1") (pintype "passive"))
      (node (ref "U$2") (pin "8") (pinfunction "PH_8") (pintype "passive"))
    )
    (net (code "25") (name "PH6") (class "Default")
      (node (ref "C14") (pin "2") (pinfunction "2_2") (pintype "passive"))
      (node (ref "D3") (pin "3") (pinfunction "K_3") (pintype "passive"))
      (node (ref "L3") (pin "1") (pinfunction "1_1") (pintype "passive"))
      (node (ref "U$3") (pin "8") (pinfunction "PH_8") (pintype "passive"))
    )
    (net (code "26") (name "PH12") (class "Default")
      (node (ref "C3") (pin "2") (pinfunction "2_2") (pintype "passive"))
      (node (ref "D1") (pin "3") (pinfunction "K_3") (pintype "passive"))
      (node (ref "L2") (pin "1") (pinfunction "1_1") (pintype "passive"))
      (node (ref "U$1") (pin "8") (pinfunction "PH_8") (pintype "passive"))
    )
    (net (code "27") (name "RGB_B") (class "Default")
      (node (ref "R12") (pin "2") (pinfunction "2_2") (pintype "passive"))
      (node (ref "U$5") (pin "2") (pinfunction "P1.0_2") (pintype "bidirectional"))
    )
    (net (code "28") (name "RGB_G") (class "Default")
      (node (ref "R15") (pin "2") (pinfunction "2_2") (pintype "passive"))
      (node (ref "U$5") (pin "4") (pinfunction "P1.2_4") (pintype "bidirectional"))
    )
    (net (code "29") (name "RGB_R") (class "Default")
      (node (ref "R13") (pin "2") (pinfunction "2_2") (pintype "passive"))
      (node (ref "U$5") (pin "3") (pinfunction "P1.1_3") (pintype "bidirectional"))
    )
    (net (code "30") (name "RST") (class "Default")
      (node (ref "C23") (pin "1") (pinfunction "1_1") (pintype "passive"))
      (node (ref "JTAG") (pin "11") (pinfunction "KL_11") (pintype "passive"))
      (node (ref "R11") (pin "2") (pinfunction "2_2") (pintype "passive"))
      (node (ref "U$5") (pin "10") (pinfunction "RTS_10") (pintype "bidirectional"))
    )
    (net (code "31") (name "SW3_3") (class "Default")
      (node (ref "L4") (pin "1") (pinfunction "1_1") (pintype "passive"))
      (node (ref "U$4") (pin "9") (pinfunction "SW_9") (pintype "passive"))
    )
    (net (code "32") (name "TCK") (class "Default")
      (node (ref "JTAG") (pin "7") (pinfunction "KL_7") (pintype "passive"))
      (node (ref "U$5") (pin "6") (pinfunction "P1.4_6") (pintype "bidirectional"))
    )
    (net (code "33") (name "TDI{slash}VPP") (class "Default")
      (node (ref "JTAG") (pin "3") (pinfunction "KL_3") (pintype "passive"))
      (node (ref "U$5") (pin "8") (pinfunction "P1.6_8") (pintype "bidirectional"))
    )
    (net (code "34") (name "TDO{slash}TDI") (class "Default")
      (node (ref "JTAG") (pin "1") (pinfunction "KL_1") (pintype "passive"))
      (node (ref "U$5") (pin "9") (pinfunction "P1.7_9") (pintype "bidirectional"))
    )
    (net (code "35") (name "TEST{slash}VPP") (class "Default")
      (node (ref "JTAG") (pin "8") (pinfunction "KL_8") (pintype "passive"))
      (node (ref "U$5") (pin "11") (pinfunction "TEST_11") (pintype "bidirectional"))
    )
    (net (code "36") (name "TMS") (class "Default")
      (node (ref "JTAG") (pin "5") (pinfunction "KL_5") (pintype "passive"))
      (node (ref "U$5") (pin "7") (pinfunction "P1.5_7") (pintype "bidirectional"))
    )
    (net (code "37") (name "VCC") (class "Default")
      (node (ref "C1") (pin "2") (pinfunction "2_2") (pintype "passive"))
      (node (ref "C10") (pin "2") (pinfunction "2_2") (pintype "passive"))
      (node (ref "C11") (pin "2") (pinfunction "2_2") (pintype "passive"))
      (node (ref "C12") (pin "2") (pinfunction "2_2") (pintype "passive"))
      (node (ref "C13") (pin "2") (pinfunction "2_2") (pintype "passive"))
      (node (ref "C16") (pin "2") (pinfunction "2_2") (pintype "passive"))
      (node (ref "C17") (pin "2") (pinfunction "2_2") (pintype "passive"))
      (node (ref "C18") (pin "2") (pinfunction "2_2") (pintype "passive"))
      (node (ref "C2") (pin "2") (pinfunction "2_2") (pintype "passive"))
      (node (ref "C20") (pin "1") (pinfunction "1_1") (pintype "passive"))
      (node (ref "C6") (pin "2") (pinfunction "2_2") (pintype "passive"))
      (node (ref "C7") (pin "2") (pinfunction "2_2") (pintype "passive"))
      (node (ref "C8") (pin "2") (pinfunction "2_2") (pintype "passive"))
      (node (ref "J1") (pin "2") (pinfunction "2_2") (pintype "passive"))
      (node (ref "J1") (pin "3") (pinfunction "3_3") (pintype "passive"))
      (node (ref "J2") (pin "2") (pinfunction "2_2") (pintype "passive"))
      (node (ref "J2") (pin "3") (pinfunction "3_3") (pintype "passive"))
      (node (ref "PL5") (pin "2") (pinfunction "S_2") (pintype "passive"))
      (node (ref "R17") (pin "1") (pinfunction "1_1") (pintype "passive"))
      (node (ref "U$1") (pin "7") (pinfunction "VIN_7") (pintype "passive"))
      (node (ref "U$2") (pin "7") (pinfunction "VIN_7") (pintype "passive"))
      (node (ref "U$3") (pin "7") (pinfunction "VIN_7") (pintype "passive"))
      (node (ref "U$4") (pin "2") (pinfunction "VIN_2") (pintype "passive"))
      (node (ref "U$4") (pin "3") (pinfunction "EN_3") (pintype "passive"))
    )
    (net (code "38") (name "VCC_3_3") (class "Default")
      (node (ref "C19") (pin "1") (pinfunction "1_1") (pintype "passive"))
      (node (ref "C21") (pin "1") (pinfunction "1_1") (pintype "passive"))
      (node (ref "C22") (pin "1") (pinfunction "1_1") (pintype "passive"))
      (node (ref "L4") (pin "2") (pinfunction "2_2") (pintype "passive"))
      (node (ref "Q4") (pin "2") (pinfunction "S_2") (pintype "passive"))
      (node (ref "R10") (pin "2") (pinfunction "2_2") (pintype "passive"))
      (node (ref "R11") (pin "1") (pinfunction "1_1") (pintype "passive"))
      (node (ref "U$4") (pin "10") (pinfunction "VOS_10") (pintype "passive"))
      (node (ref "U$4") (pin "8") (pinfunction "SLEEP_8") (pintype "passive"))
      (node (ref "U$5") (pin "1") (pinfunction "VCC_1") (pintype "bidirectional"))
      (node (ref "VCC") (pin "2") (pinfunction "S_2") (pintype "passive"))
    )
    (net (code "39") (name "VCC_TARGET") (class "Default")
      (node (ref "JTAG") (pin "4") (pinfunction "KL_4") (pintype "passive"))
      (node (ref "VCC") (pin "1") (pinfunction "S_1") (pintype "passive"))
    )
    (net (code "40") (name "VCC_TOOL") (class "Default")
      (node (ref "JTAG") (pin "2") (pinfunction "KL_2") (pintype "passive"))
      (node (ref "VCC") (pin "3") (pinfunction "S_3") (pintype "passive"))
    )
    (net (code "41") (name "VOUT5") (class "Default")
      (node (ref "C5") (pin "1") (pinfunction "+_1") (pintype "passive"))
      (node (ref "L1") (pin "2") (pinfunction "2_2") (pintype "passive"))
      (node (ref "PL1") (pin "2") (pinfunction "S_2") (pintype "passive"))
      (node (ref "PL2") (pin "2") (pinfunction "S_2") (pintype "passive"))
      (node (ref "PL3") (pin "2") (pinfunction "S_2") (pintype "passive"))
      (node (ref "PL4") (pin "2") (pinfunction "S_2") (pintype "passive"))
      (node (ref "PL6") (pin "2") (pinfunction "S_2") (pintype "passive"))
      (node (ref "R2") (pin "2") (pinfunction "2_2") (pintype "passive"))
      (node (ref "R4") (pin "2") (pinfunction "2_2") (pintype "passive"))
    )
    (net (code "42") (name "VOUT6") (class "Default")
      (node (ref "C15") (pin "1") (pinfunction "+_1") (pintype "passive"))
      (node (ref "L3") (pin "2") (pinfunction "2_2") (pintype "passive"))
      (node (ref "PL11") (pin "3") (pinfunction "S_3") (pintype "passive"))
      (node (ref "PL11") (pin "4") (pinfunction "S_4") (pintype "passive"))
      (node (ref "PL13") (pin "3") (pinfunction "S_3") (pintype "passive"))
      (node (ref "PL13") (pin "4") (pinfunction "S_4") (pintype "passive"))
      (node (ref "R7") (pin "2") (pinfunction "2_2") (pintype "passive"))
      (node (ref "R9") (pin "2") (pinfunction "2_2") (pintype "passive"))
    )
    (net (code "43") (name "VOUT12") (class "Default")
      (node (ref "C9") (pin "1") (pinfunction "+_1") (pintype "passive"))
      (node (ref "L2") (pin "2") (pinfunction "2_2") (pintype "passive"))
      (node (ref "PL10") (pin "2") (pinfunction "S_2") (pintype "passive"))
      (node (ref "PL9") (pin "2") (pinfunction "S_2") (pintype "passive"))
      (node (ref "R1") (pin "2") (pinfunction "2_2") (pintype "passive"))
      (node (ref "R6") (pin "2") (pinfunction "2_2") (pintype "passive"))
    )
    (net (code "44") (name "unconnected-(JTAGB-KL-Pad10)") (class "Default")
      (node (ref "JTAG") (pin "10") (pinfunction "KL_10") (pintype "passive"))
    )
    (net (code "45") (name "unconnected-(JTAGD-KL-Pad12)") (class "Default")
      (node (ref "JTAG") (pin "12") (pinfunction "KL_12") (pintype "passive"))
    )
    (net (code "46") (name "unconnected-(JTAGE-KL-Pad13)") (class "Default")
      (node (ref "JTAG") (pin "13") (pinfunction "KL_13") (pintype "passive"))
    )
    (net (code "47") (name "unconnected-(JTAGF-KL-Pad14)") (class "Default")
      (node (ref "JTAG") (pin "14") (pinfunction "KL_14") (pintype "passive"))
    )
    (net (code "48") (name "unconnected-(JTAGK-KL-Pad6)") (class "Default")
      (node (ref "JTAG") (pin "6") (pinfunction "KL_6") (pintype "passive"))
    )
    (net (code "49") (name "unconnected-(U$4-NC-Pad4)") (class "Default")
      (node (ref "U$4") (pin "4") (pinfunction "NC_4") (pintype "passive"))
    )
  )
)
